# motor_driver_v1_0.net
KiCad netlist of a schematic drawn in EAGLE
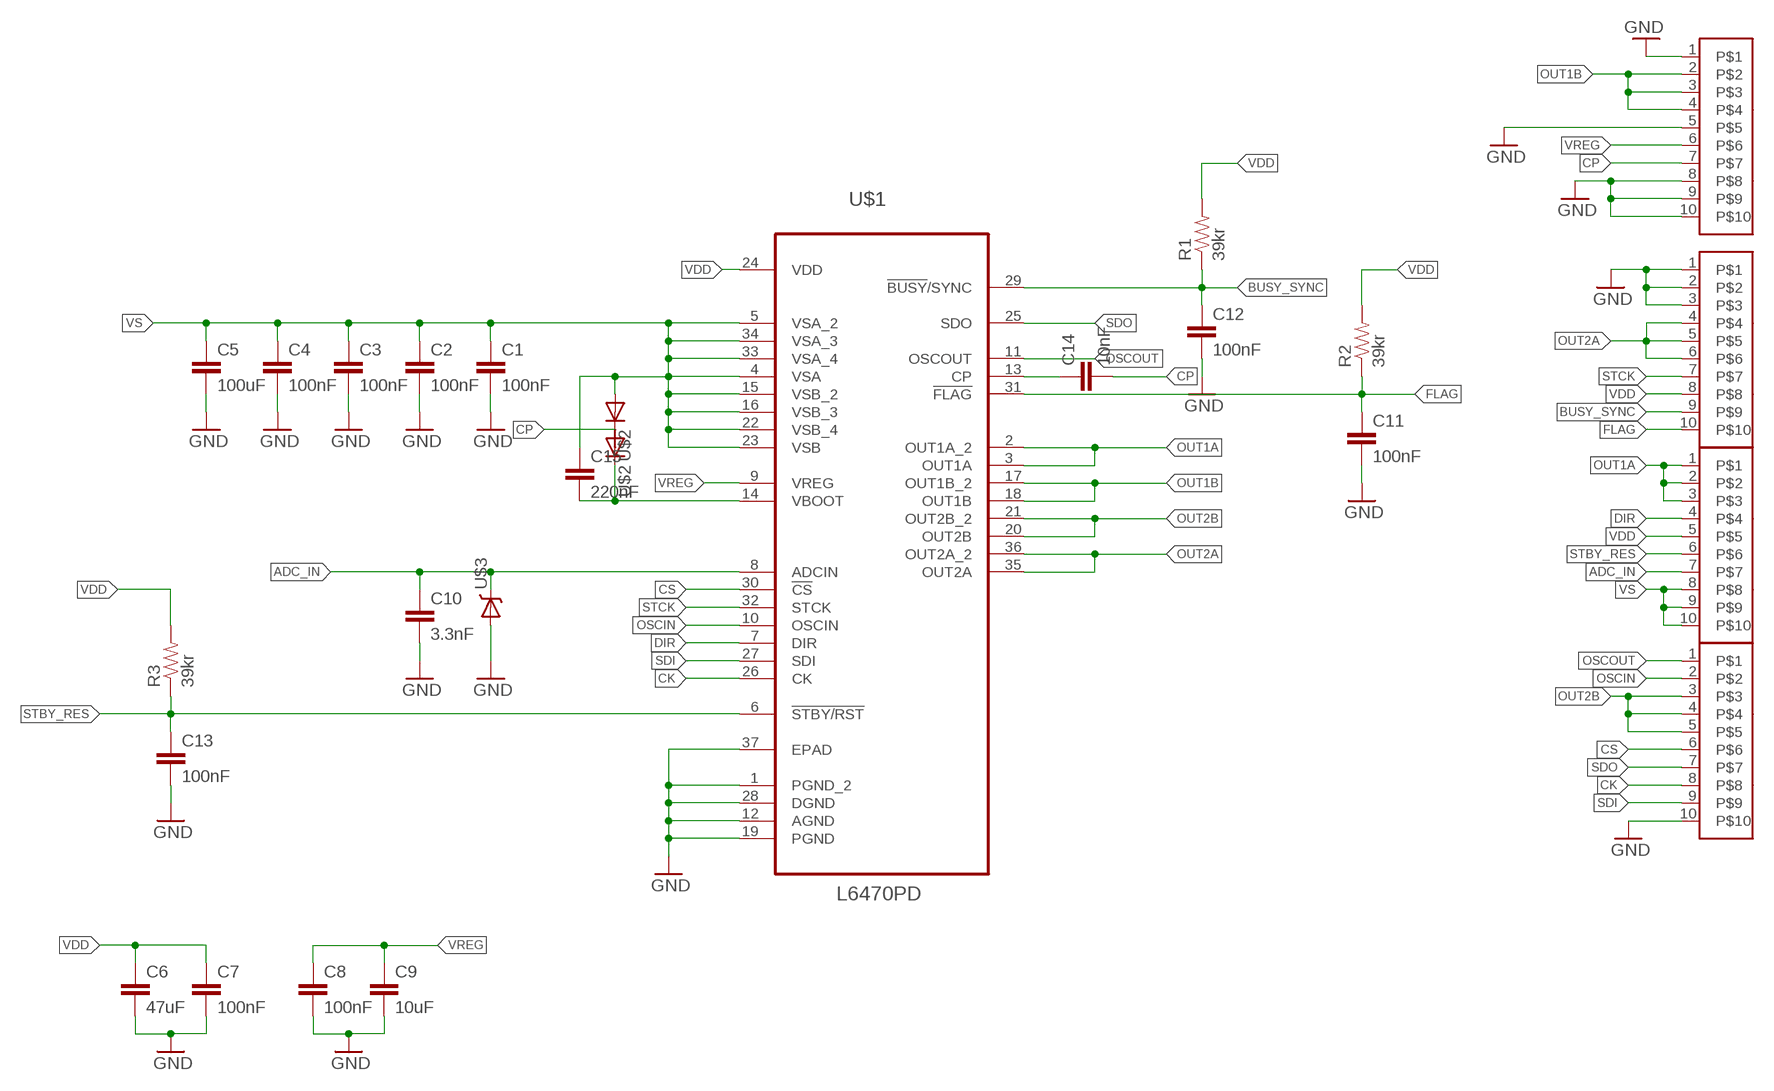
[diagram p0: schematic, sheet 1]

(export (version "E")
  (design (tool "Eeschema 10.0.6"))
  (components
    (comp (ref "C1")
      (value "100nF")
      (footprint "eagle-import:0603-CAP")
      (libsource (lib "eagle-import") (part "CAP0603"))
    )
    (comp (ref "C2")
      (value "100nF")
      (footprint "eagle-import:0603-CAP")
      (libsource (lib "eagle-import") (part "CAP0603"))
    )
    (comp (ref "C3")
      (value "100nF")
      (footprint "eagle-import:0603-CAP")
      (libsource (lib "eagle-import") (part "CAP0603"))
    )
    (comp (ref "C4")
      (value "100nF")
      (footprint "eagle-import:0603-CAP")
      (libsource (lib "eagle-import") (part "CAP0603"))
    )
    (comp (ref "C5")
      (value "100uF")
      (footprint "eagle-import:CAP-10X12")
      (libsource (lib "eagle-import") (part "CAP"))
    )
    (comp (ref "C6")
      (value "47uF")
      (footprint "eagle-import:1206-CAP")
      (libsource (lib "eagle-import") (part "CAP1206"))
    )
    (comp (ref "C7")
      (value "100nF")
      (footprint "eagle-import:0603-CAP")
      (libsource (lib "eagle-import") (part "CAP0603"))
    )
    (comp (ref "C8")
      (value "100nF")
      (footprint "eagle-import:0603-CAP")
      (libsource (lib "eagle-import") (part "CAP0603"))
    )
    (comp (ref "C9")
      (value "10uF")
      (footprint "eagle-import:0805-CAP")
      (libsource (lib "eagle-import") (part "CAP0805"))
    )
    (comp (ref "C10")
      (value "3.3nF")
      (footprint "eagle-import:0603-CAP")
      (libsource (lib "eagle-import") (part "CAP0603"))
    )
    (comp (ref "C11")
      (value "100nF")
      (footprint "eagle-import:0603-CAP")
      (libsource (lib "eagle-import") (part "CAP0603"))
    )
    (comp (ref "C12")
      (value "100nF")
      (footprint "eagle-import:0603-CAP")
      (libsource (lib "eagle-import") (part "CAP0603"))
    )
    (comp (ref "C13")
      (value "100nF")
      (footprint "eagle-import:0603-CAP")
      (libsource (lib "eagle-import") (part "CAP0603"))
    )
    (comp (ref "C14")
      (value "10nF")
      (footprint "eagle-import:0603-CAP")
      (libsource (lib "eagle-import") (part "CAP0603"))
    )
    (comp (ref "C15")
      (value "220nF")
      (footprint "eagle-import:0603-CAP")
      (libsource (lib "eagle-import") (part "CAP0603"))
    )
    (comp (ref "R1")
      (value "39kr")
      (footprint "eagle-import:0603-RES")
      (libsource (lib "eagle-import") (part "RESISTOR0603-RES"))
    )
    (comp (ref "R2")
      (value "39kr")
      (footprint "eagle-import:0603-RES")
      (libsource (lib "eagle-import") (part "RESISTOR0603-RES"))
    )
    (comp (ref "R3")
      (value "39kr")
      (footprint "eagle-import:0603-RES")
      (libsource (lib "eagle-import") (part "RESISTOR0603-RES"))
    )
    (comp (ref "U$1")
      (value "L6470PD")
      (footprint "eagle-import:SOP65P1400X360-37N")
      (libsource (lib "eagle-import") (part "L6470PD"))
    )
    (comp (ref "U$2")
      (value "BAV99")
      (footprint "eagle-import:BAV99")
      (libsource (lib "eagle-import") (part "BAV99"))
    )
    (comp (ref "U$3")
      (value "BZX585")
      (footprint "eagle-import:BZX585")
      (libsource (lib "eagle-import") (part "BZX585"))
    )
    (comp (ref "U$4")
      (value "CON_TH_10PINS")
      (footprint "eagle-import:CON_TH_10POS")
      (libsource (lib "eagle-import") (part "CON_TH_10PINS"))
    )
    (comp (ref "U$5")
      (value "CON_TH_10PINS")
      (footprint "eagle-import:CON_TH_10POS")
      (libsource (lib "eagle-import") (part "CON_TH_10PINS"))
    )
    (comp (ref "U$6")
      (value "CON_TH_10PINS")
      (footprint "eagle-import:CON_TH_10POS")
      (libsource (lib "eagle-import") (part "CON_TH_10PINS"))
    )
    (comp (ref "U$7")
      (value "CON_TH_10PINS")
      (footprint "eagle-import:CON_TH_10POS")
      (libsource (lib "eagle-import") (part "CON_TH_10PINS"))
    )
  )
  (nets
    (net (code "1") (name "ADC_IN") (class "Default")
      (node (ref "C10") (pin "P$1") (pinfunction "1_P$1") (pintype "passive"))
      (node (ref "U$1") (pin "8") (pinfunction "ADCIN_8") (pintype "input"))
      (node (ref "U$3") (pin "P$1") (pinfunction "1_P$1") (pintype "passive"))
      (node (ref "U$4") (pin "7") (pinfunction "P$7_7") (pintype "bidirectional"))
    )
    (net (code "2") (name "BUSY_SYNC") (class "Default")
      (node (ref "C12") (pin "P$1") (pinfunction "1_P$1") (pintype "passive"))
      (node (ref "R1") (pin "1") (pinfunction "1_1") (pintype "passive"))
      (node (ref "U$1") (pin "29") (pinfunction "~{BUSY}/SYNC_29") (pintype "output"))
      (node (ref "U$5") (pin "9") (pinfunction "P$9_9") (pintype "bidirectional"))
    )
    (net (code "3") (name "CK") (class "Default")
      (node (ref "U$1") (pin "26") (pinfunction "CK_26") (pintype "input"))
      (node (ref "U$7") (pin "8") (pinfunction "P$8_8") (pintype "bidirectional"))
    )
    (net (code "4") (name "CP") (class "Default")
      (node (ref "C14") (pin "P$2") (pinfunction "2_P$2") (pintype "passive"))
      (node (ref "U$2") (pin "P$3") (pinfunction "3_P$3") (pintype "passive"))
      (node (ref "U$6") (pin "7") (pinfunction "P$7_7") (pintype "bidirectional"))
    )
    (net (code "5") (name "CS") (class "Default")
      (node (ref "U$1") (pin "30") (pinfunction "~{CS}_30") (pintype "input"))
      (node (ref "U$7") (pin "6") (pinfunction "P$6_6") (pintype "bidirectional"))
    )
    (net (code "6") (name "DIR") (class "Default")
      (node (ref "U$1") (pin "7") (pinfunction "DIR_7") (pintype "passive"))
      (node (ref "U$4") (pin "4") (pinfunction "P$4_4") (pintype "bidirectional"))
    )
    (net (code "7") (name "FLAG") (class "Default")
      (node (ref "C11") (pin "P$1") (pinfunction "1_P$1") (pintype "passive"))
      (node (ref "R2") (pin "1") (pinfunction "1_1") (pintype "passive"))
      (node (ref "U$1") (pin "31") (pinfunction "~{FLAG}_31") (pintype "output"))
      (node (ref "U$5") (pin "10") (pinfunction "P$10_10") (pintype "bidirectional"))
    )
    (net (code "8") (name "GND") (class "Default")
      (node (ref "C1") (pin "P$2") (pinfunction "2_P$2") (pintype "passive"))
      (node (ref "C10") (pin "P$2") (pinfunction "2_P$2") (pintype "passive"))
      (node (ref "C11") (pin "P$2") (pinfunction "2_P$2") (pintype "passive"))
      (node (ref "C12") (pin "P$2") (pinfunction "2_P$2") (pintype "passive"))
      (node (ref "C13") (pin "P$2") (pinfunction "2_P$2") (pintype "passive"))
      (node (ref "C2") (pin "P$2") (pinfunction "2_P$2") (pintype "passive"))
      (node (ref "C3") (pin "P$2") (pinfunction "2_P$2") (pintype "passive"))
      (node (ref "C4") (pin "P$2") (pinfunction "2_P$2") (pintype "passive"))
      (node (ref "C5") (pin "P$2") (pinfunction "2_P$2") (pintype "passive"))
      (node (ref "C6") (pin "P$2") (pinfunction "2_P$2") (pintype "passive"))
      (node (ref "C7") (pin "P$2") (pinfunction "2_P$2") (pintype "passive"))
      (node (ref "C8") (pin "P$2") (pinfunction "2_P$2") (pintype "passive"))
      (node (ref "C9") (pin "P$2") (pinfunction "2_P$2") (pintype "passive"))
      (node (ref "U$1") (pin "1") (pinfunction "PGND_2_1") (pintype "passive"))
      (node (ref "U$1") (pin "12") (pinfunction "AGND_12") (pintype "passive"))
      (node (ref "U$1") (pin "19") (pinfunction "PGND_19") (pintype "passive"))
      (node (ref "U$1") (pin "28") (pinfunction "DGND_28") (pintype "passive"))
      (node (ref "U$1") (pin "37") (pinfunction "EPAD_37") (pintype "passive"))
      (node (ref "U$3") (pin "P$2") (pinfunction "2_P$2") (pintype "passive"))
      (node (ref "U$5") (pin "1") (pinfunction "P$1_1") (pintype "bidirectional"))
      (node (ref "U$5") (pin "2") (pinfunction "P$2_2") (pintype "bidirectional"))
      (node (ref "U$5") (pin "3") (pinfunction "P$3_3") (pintype "bidirectional"))
      (node (ref "U$6") (pin "1") (pinfunction "P$1_1") (pintype "bidirectional"))
      (node (ref "U$6") (pin "10") (pinfunction "P$10_10") (pintype "bidirectional"))
      (node (ref "U$6") (pin "5") (pinfunction "P$5_5") (pintype "bidirectional"))
      (node (ref "U$6") (pin "8") (pinfunction "P$8_8") (pintype "bidirectional"))
      (node (ref "U$6") (pin "9") (pinfunction "P$9_9") (pintype "bidirectional"))
      (node (ref "U$7") (pin "10") (pinfunction "P$10_10") (pintype "bidirectional"))
    )
    (net (code "9") (name "Net-(C14-1)") (class "Default")
      (node (ref "C14") (pin "P$1") (pinfunction "1_P$1") (pintype "passive"))
      (node (ref "U$1") (pin "13") (pinfunction "CP_13") (pintype "output"))
    )
    (net (code "10") (name "Net-(C15-2)") (class "Default")
      (node (ref "C15") (pin "P$2") (pinfunction "2_P$2") (pintype "passive"))
      (node (ref "U$1") (pin "14") (pinfunction "VBOOT_14") (pintype "power_in"))
      (node (ref "U$2") (pin "P$2") (pinfunction "2_P$2") (pintype "passive"))
    )
    (net (code "11") (name "OSCIN") (class "Default")
      (node (ref "U$1") (pin "10") (pinfunction "OSCIN_10") (pintype "input"))
      (node (ref "U$7") (pin "2") (pinfunction "P$2_2") (pintype "bidirectional"))
    )
    (net (code "12") (name "OSCOUT") (class "Default")
      (node (ref "U$1") (pin "11") (pinfunction "OSCOUT_11") (pintype "output"))
      (node (ref "U$7") (pin "1") (pinfunction "P$1_1") (pintype "bidirectional"))
    )
    (net (code "13") (name "OUT1A") (class "Default")
      (node (ref "U$1") (pin "2") (pinfunction "OUT1A_2_2") (pintype "output"))
      (node (ref "U$1") (pin "3") (pinfunction "OUT1A_3") (pintype "output"))
      (node (ref "U$4") (pin "1") (pinfunction "P$1_1") (pintype "bidirectional"))
      (node (ref "U$4") (pin "2") (pinfunction "P$2_2") (pintype "bidirectional"))
      (node (ref "U$4") (pin "3") (pinfunction "P$3_3") (pintype "bidirectional"))
    )
    (net (code "14") (name "OUT1B") (class "Default")
      (node (ref "U$1") (pin "17") (pinfunction "OUT1B_2_17") (pintype "output"))
      (node (ref "U$1") (pin "18") (pinfunction "OUT1B_18") (pintype "output"))
      (node (ref "U$6") (pin "2") (pinfunction "P$2_2") (pintype "bidirectional"))
      (node (ref "U$6") (pin "3") (pinfunction "P$3_3") (pintype "bidirectional"))
      (node (ref "U$6") (pin "4") (pinfunction "P$4_4") (pintype "bidirectional"))
    )
    (net (code "15") (name "OUT2A") (class "Default")
      (node (ref "U$1") (pin "35") (pinfunction "OUT2A_35") (pintype "output"))
      (node (ref "U$1") (pin "36") (pinfunction "OUT2A_2_36") (pintype "output"))
      (node (ref "U$5") (pin "4") (pinfunction "P$4_4") (pintype "bidirectional"))
      (node (ref "U$5") (pin "5") (pinfunction "P$5_5") (pintype "bidirectional"))
      (node (ref "U$5") (pin "6") (pinfunction "P$6_6") (pintype "bidirectional"))
    )
    (net (code "16") (name "OUT2B") (class "Default")
      (node (ref "U$1") (pin "20") (pinfunction "OUT2B_20") (pintype "output"))
      (node (ref "U$1") (pin "21") (pinfunction "OUT2B_2_21") (pintype "output"))
      (node (ref "U$7") (pin "3") (pinfunction "P$3_3") (pintype "bidirectional"))
      (node (ref "U$7") (pin "4") (pinfunction "P$4_4") (pintype "bidirectional"))
      (node (ref "U$7") (pin "5") (pinfunction "P$5_5") (pintype "bidirectional"))
    )
    (net (code "17") (name "SDI") (class "Default")
      (node (ref "U$1") (pin "27") (pinfunction "SDI_27") (pintype "input"))
      (node (ref "U$7") (pin "9") (pinfunction "P$9_9") (pintype "bidirectional"))
    )
    (net (code "18") (name "SDO") (class "Default")
      (node (ref "U$1") (pin "25") (pinfunction "SDO_25") (pintype "output"))
      (node (ref "U$7") (pin "7") (pinfunction "P$7_7") (pintype "bidirectional"))
    )
    (net (code "19") (name "STBY_RES") (class "Default")
      (node (ref "C13") (pin "P$1") (pinfunction "1_P$1") (pintype "passive"))
      (node (ref "R3") (pin "1") (pinfunction "1_1") (pintype "passive"))
      (node (ref "U$1") (pin "6") (pinfunction "~{STBY/RST}_6") (pintype "input"))
      (node (ref "U$4") (pin "6") (pinfunction "P$6_6") (pintype "bidirectional"))
    )
    (net (code "20") (name "STCK") (class "Default")
      (node (ref "U$1") (pin "32") (pinfunction "STCK_32") (pintype "input"))
      (node (ref "U$5") (pin "7") (pinfunction "P$7_7") (pintype "bidirectional"))
    )
    (net (code "21") (name "VDD") (class "Default")
      (node (ref "C6") (pin "P$1") (pinfunction "1_P$1") (pintype "passive"))
      (node (ref "C7") (pin "P$1") (pinfunction "1_P$1") (pintype "passive"))
      (node (ref "R1") (pin "2") (pinfunction "2_2") (pintype "passive"))
      (node (ref "R2") (pin "2") (pinfunction "2_2") (pintype "passive"))
      (node (ref "R3") (pin "2") (pinfunction "2_2") (pintype "passive"))
      (node (ref "U$1") (pin "24") (pinfunction "VDD_24") (pintype "power_in"))
      (node (ref "U$4") (pin "5") (pinfunction "P$5_5") (pintype "bidirectional"))
      (node (ref "U$5") (pin "8") (pinfunction "P$8_8") (pintype "bidirectional"))
    )
    (net (code "22") (name "VREG") (class "Default")
      (node (ref "C8") (pin "P$1") (pinfunction "1_P$1") (pintype "passive"))
      (node (ref "C9") (pin "P$1") (pinfunction "1_P$1") (pintype "passive"))
      (node (ref "U$1") (pin "9") (pinfunction "VREG_9") (pintype "power_in"))
      (node (ref "U$6") (pin "6") (pinfunction "P$6_6") (pintype "bidirectional"))
    )
    (net (code "23") (name "VS") (class "Default")
      (node (ref "C1") (pin "P$1") (pinfunction "1_P$1") (pintype "passive"))
      (node (ref "C15") (pin "P$1") (pinfunction "1_P$1") (pintype "passive"))
      (node (ref "C2") (pin "P$1") (pinfunction "1_P$1") (pintype "passive"))
      (node (ref "C3") (pin "P$1") (pinfunction "1_P$1") (pintype "passive"))
      (node (ref "C4") (pin "P$1") (pinfunction "1_P$1") (pintype "passive"))
      (node (ref "C5") (pin "P$1") (pinfunction "1_P$1") (pintype "passive"))
      (node (ref "U$1") (pin "15") (pinfunction "VSB_2_15") (pintype "power_in"))
      (node (ref "U$1") (pin "16") (pinfunction "VSB_3_16") (pintype "power_in"))
      (node (ref "U$1") (pin "22") (pinfunction "VSB_4_22") (pintype "power_in"))
      (node (ref "U$1") (pin "23") (pinfunction "VSB_23") (pintype "power_in"))
      (node (ref "U$1") (pin "33") (pinfunction "VSA_4_33") (pintype "power_in"))
      (node (ref "U$1") (pin "34") (pinfunction "VSA_3_34") (pintype "power_in"))
      (node (ref "U$1") (pin "4") (pinfunction "VSA_4") (pintype "power_in"))
      (node (ref "U$1") (pin "5") (pinfunction "VSA_2_5") (pintype "power_in"))
      (node (ref "U$2") (pin "P$1") (pinfunction "1_P$1") (pintype "passive"))
      (node (ref "U$4") (pin "10") (pinfunction "P$10_10") (pintype "bidirectional"))
      (node (ref "U$4") (pin "8") (pinfunction "P$8_8") (pintype "bidirectional"))
      (node (ref "U$4") (pin "9") (pinfunction "P$9_9") (pintype "bidirectional"))
    )
  )
)
